# pca10156_sheet1_connections.net
KiCad netlist of a schematic drawn in Altium Designer
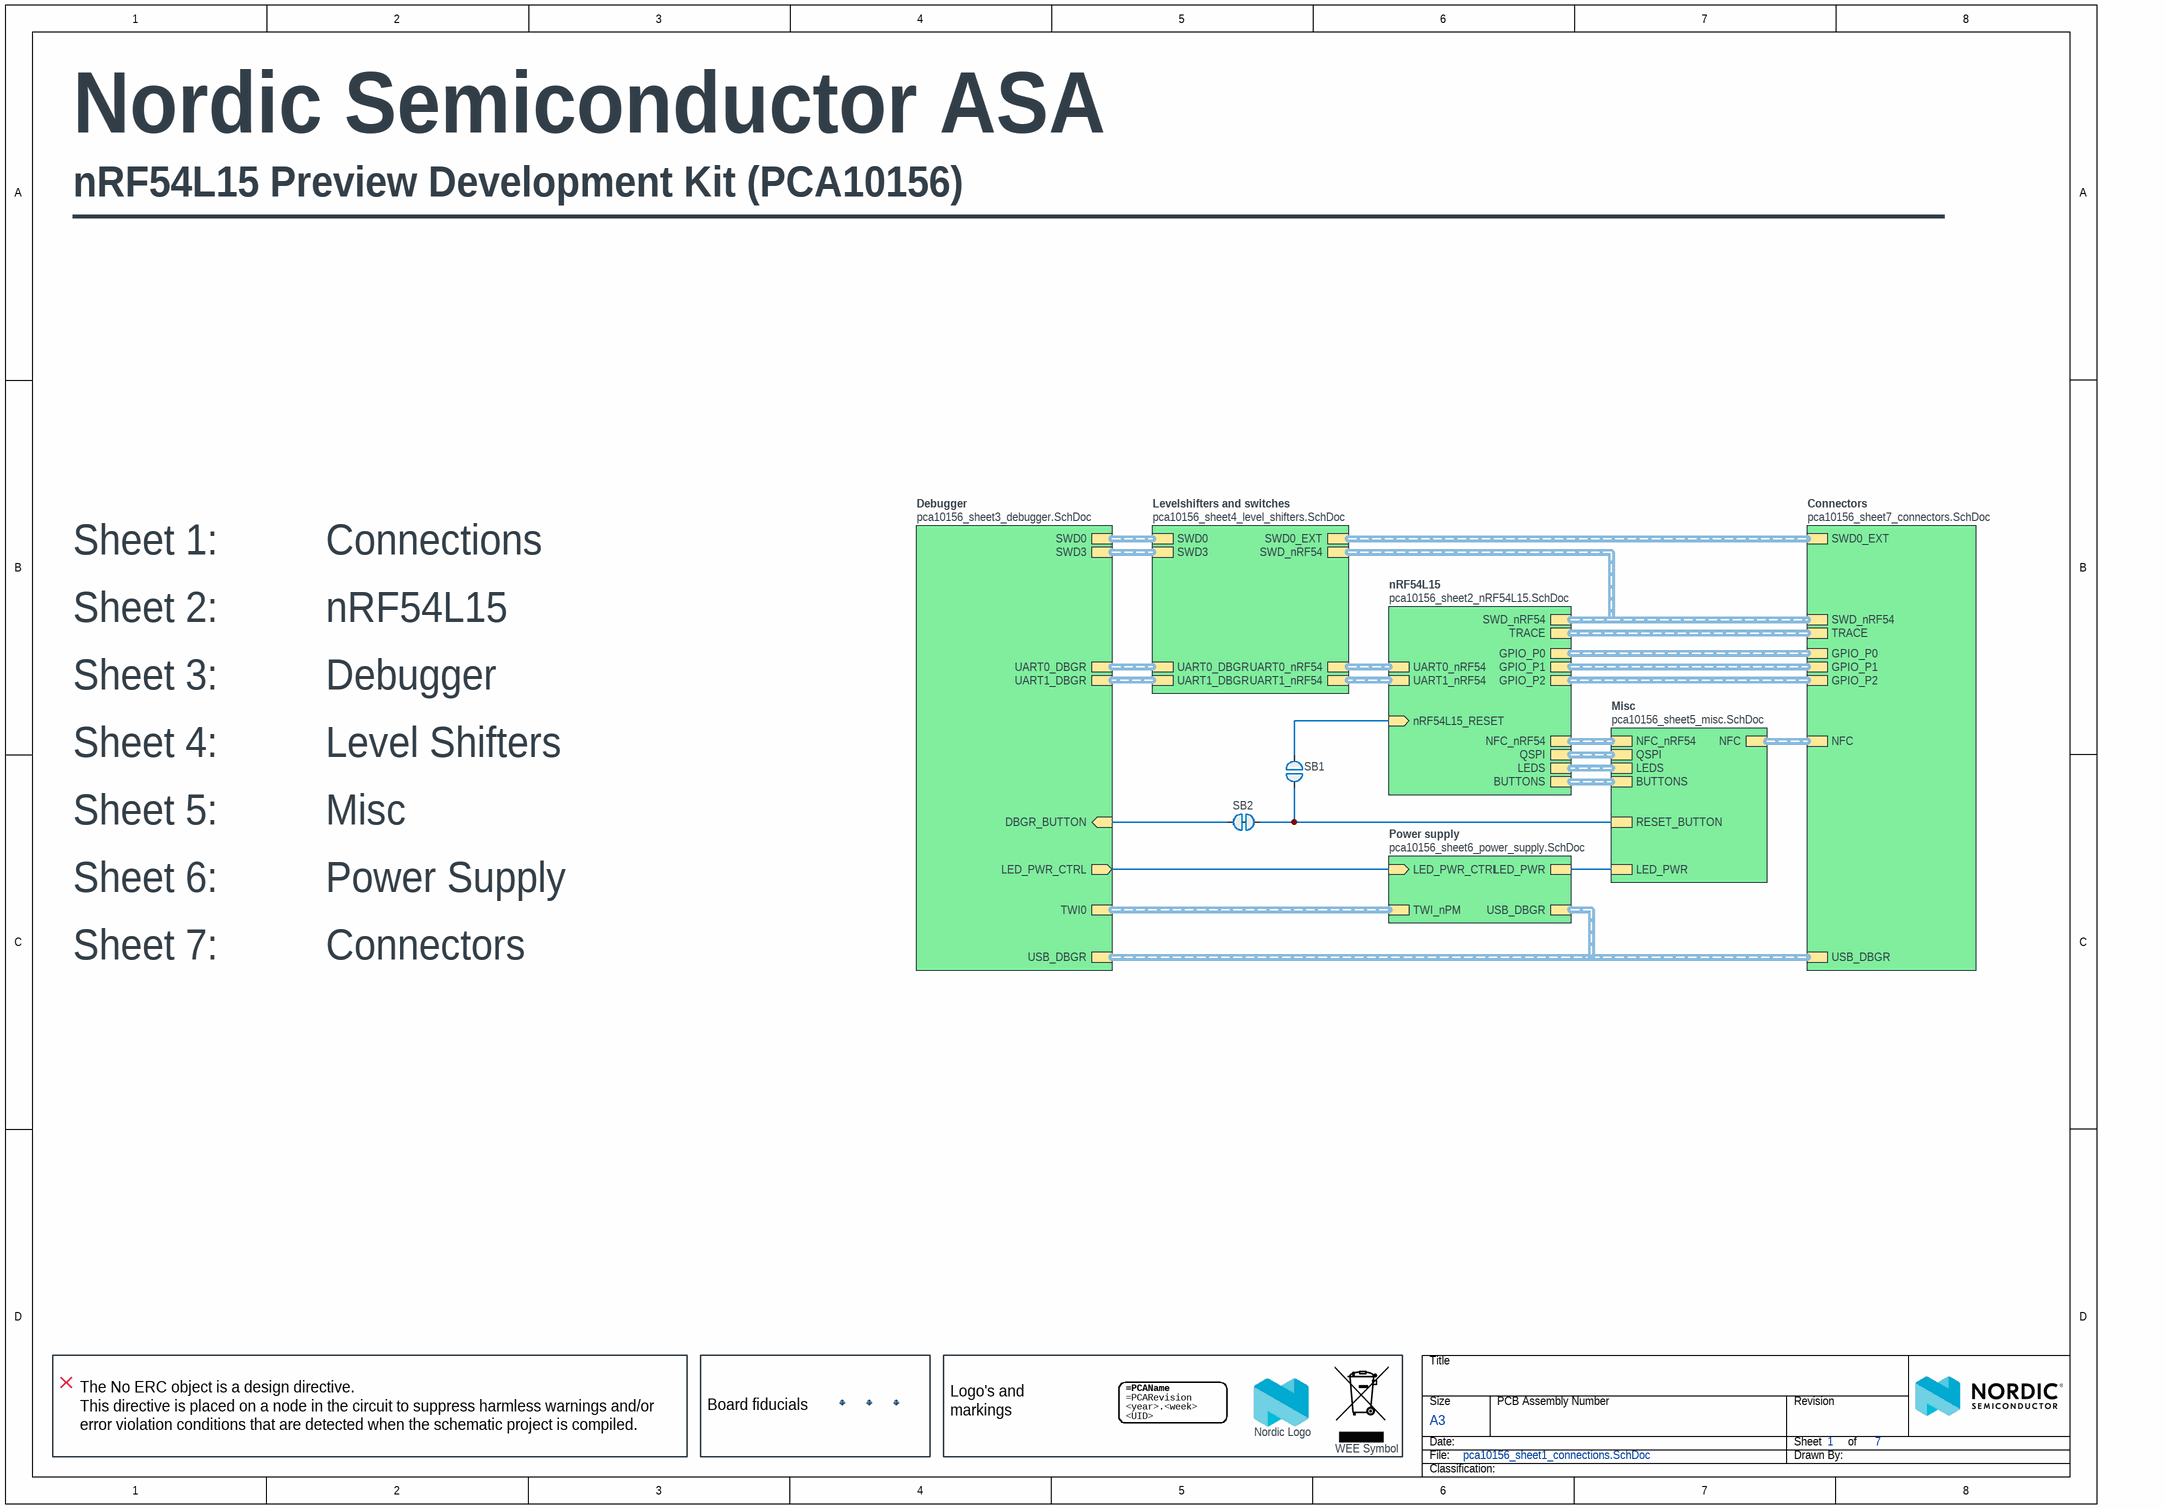
[diagram p0: pca10156_sheet1_connections.SchDoc]

(export (version "E")
  (design (tool "Eeschema 10.0.6"))
  (components
    (comp (ref "Fid1")
      (value "Fiducial mark")
      (footprint "Fiducial")
      (description "Fiducial Mark")
      (fields
        (field (name "PART NUMBER") "Fid-Mark")
        (field (name "MANUFACTURER") "N.A.")
        (field (name "AUTHOR") "rsk")
      )
      (libsource (lib "AltiumLib") (part "Fiducial"))
    )
    (comp (ref "Fid2")
      (value "Fiducial mark")
      (footprint "Fiducial")
      (description "Fiducial Mark")
      (fields
        (field (name "PART NUMBER") "Fid-Mark")
        (field (name "MANUFACTURER") "N.A.")
        (field (name "AUTHOR") "rsk")
      )
      (libsource (lib "AltiumLib") (part "Fiducial"))
    )
    (comp (ref "Fid3")
      (value "Fiducial mark")
      (footprint "Fiducial")
      (description "Fiducial Mark")
      (fields
        (field (name "PART NUMBER") "Fid-Mark")
        (field (name "MANUFACTURER") "N.A.")
        (field (name "AUTHOR") "rsk")
      )
      (libsource (lib "AltiumLib") (part "Fiducial"))
    )
    (comp (ref "LABEL1")
      (value "12x12mm")
      (footprint "LabelSilk_12x12")
      (description "PCA version label, stick-on, 12x12mm")
      (fields
        (field (name "PART NUMBER") "Label_12x12")
        (field (name "MANUFACTURER") "Ellco Etikett")
        (field (name "AUTHOR") "hany")
      )
      (libsource (lib "AltiumLib") (part "Label_Stick-on-4-lines"))
    )
    (comp (ref "LOGO1")
      (value "Nordic Logo")
      (footprint "NORDIC_LOGO_LYING")
      (description "Nordic logo lying")
      (fields
        (field (name "PART NUMBER") "Nordic Logo lying")
        (field (name "MANUFACTURER") "N.A.")
        (field (name "AUTHOR") "rsk")
      )
      (libsource (lib "AltiumLib") (part "Nordic Logo"))
    )
    (comp (ref "LOGO2")
      (value "WEE Symbol")
      (footprint "WEE_3x4.5mm")
      (description "WEEE Directive symbol")
      (fields
        (field (name "PART NUMBER") "WEEE Symbol 3x4.5mm")
        (field (name "MANUFACTURER") "N.A.")
        (field (name "AUTHOR") "rsk")
      )
      (libsource (lib "AltiumLib") (part "WEEE Directive Logo"))
    )
    (comp (ref "SB1")
      (value "Solderbridge")
      (footprint "Solderbridge")
      (fields (field (name "MANUFACTURER") "N.A.") (field (name "AUTHOR") "rsk"))
      (libsource (lib "AltiumLib") (part "SOLDERBRIDGE"))
    )
    (comp (ref "SB2")
      (value "Solderbridge")
      (footprint "Solderbridge_Shorted")
      (description "Shorted Solderbridge")
      (fields
        (field (name "PART NUMBER") "Solderbridge Shorted")
        (field (name "MANUFACTURER") "N.A.")
        (field (name "AUTHOR") "rsk")
      )
      (libsource (lib "AltiumLib") (part "SOLDERBRIDGE_SHORTED"))
    )
  )
  (nets
    (net (code "2") (name "/DBGR_BUTTON") (class "Default")
      (node (ref "SB2") (pin "2") (pinfunction "1_2") (pintype "passive"))
    )
    (net (code "12") (name "/RESET_BUTTON") (class "Default")
      (node (ref "SB1") (pin "2") (pinfunction "1_2") (pintype "passive"))
      (node (ref "SB2") (pin "1") (pinfunction "0_1") (pintype "passive"))
    )
    (net (code "24") (name "/nRF54L15_RESET") (class "Default")
      (node (ref "SB1") (pin "1") (pinfunction "0_1") (pintype "passive"))
    )
  )
)
